# MCU_M_V1.net
KiCad netlist of a schematic drawn in Altium Designer
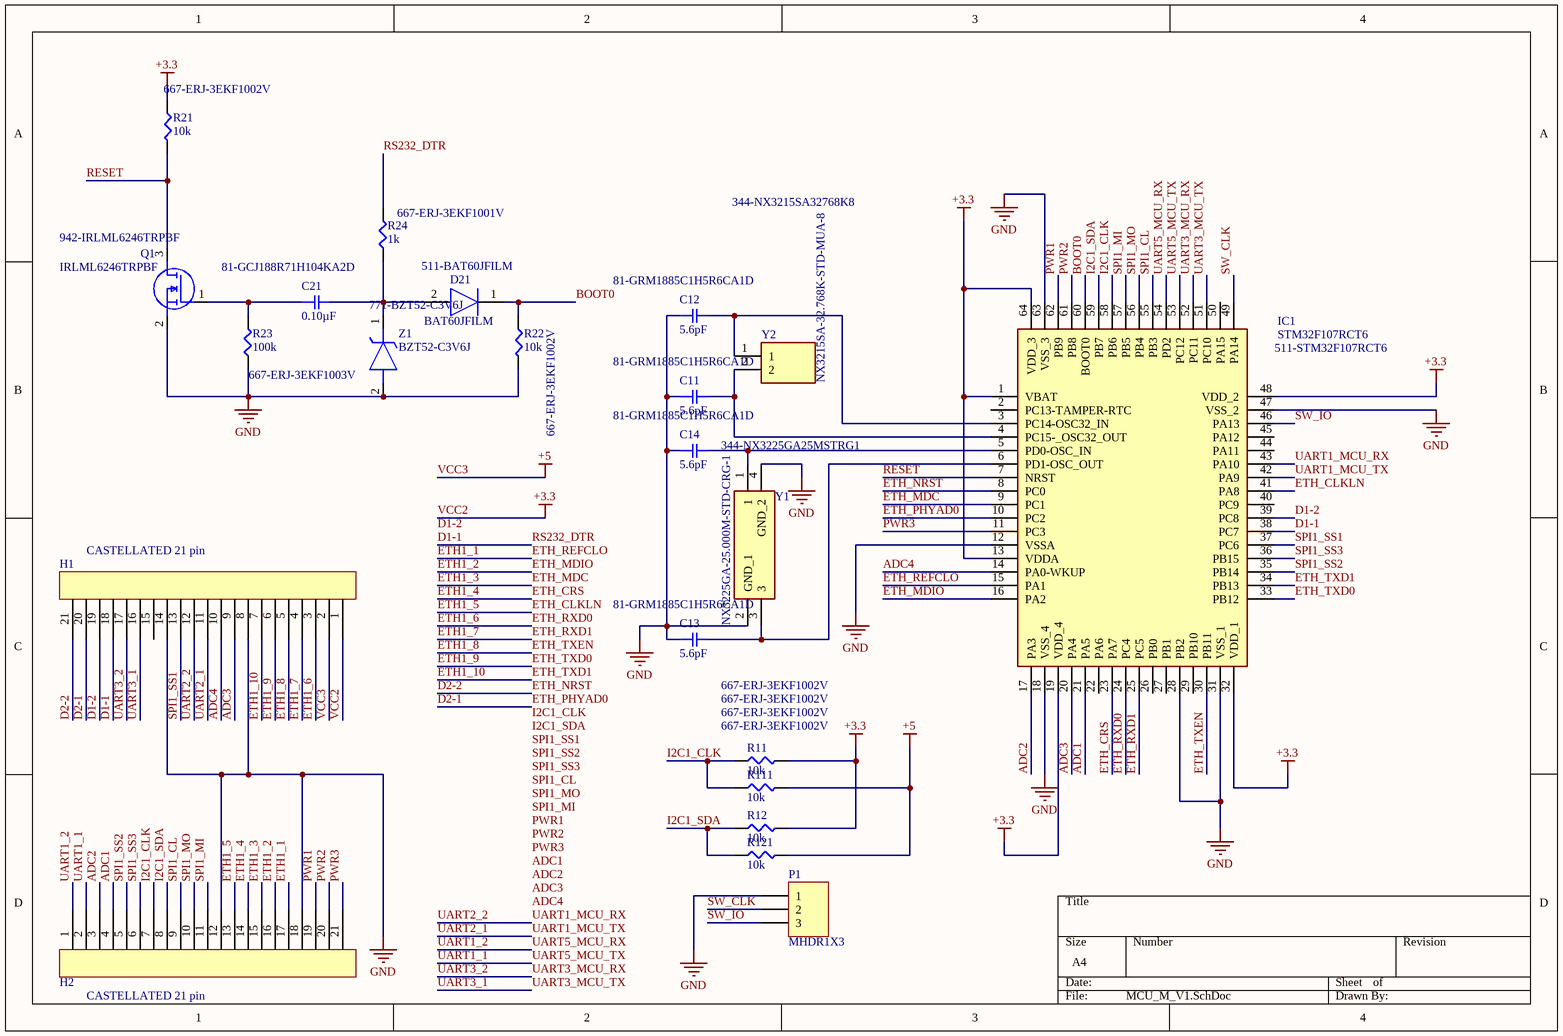
[diagram p0: MCU_M_V1.SchDoc]

(export (version "E")
  (design (tool "Eeschema 10.0.6"))
  (components
    (comp (ref "C11")
      (value "5.6pF")
      (footprint "SMD-0603C")
      (description "CAP CER 5.6PF 50V NP0 0603")
      (fields
        (field (name "DIGI-KEY PART NUMBER") "490-12723-1-ND")
        (field (name "PART NUMBER") "GRM1885C1H5R6CA01D")
        (field (name "SUPPLIER PART NUMBER 1") "81-GRM1885C1H5R6CA1D")
      )
      (libsource (lib "capacitor_murata_0603") (part "GRM1885C1H5R6CA01D"))
    )
    (comp (ref "C12")
      (value "5.6pF")
      (footprint "SMD-0603C")
      (description "CAP CER 5.6PF 50V NP0 0603")
      (fields
        (field (name "DIGI-KEY PART NUMBER") "490-12723-1-ND")
        (field (name "PART NUMBER") "GRM1885C1H5R6CA01D")
        (field (name "SUPPLIER PART NUMBER 1") "81-GRM1885C1H5R6CA1D")
      )
      (libsource (lib "capacitor_murata_0603") (part "GRM1885C1H5R6CA01D"))
    )
    (comp (ref "C13")
      (value "5.6pF")
      (footprint "SMD-0603C")
      (description "CAP CER 5.6PF 50V NP0 0603")
      (fields
        (field (name "DIGI-KEY PART NUMBER") "490-12723-1-ND")
        (field (name "PART NUMBER") "GRM1885C1H5R6CA01D")
        (field (name "SUPPLIER PART NUMBER 1") "81-GRM1885C1H5R6CA1D")
      )
      (libsource (lib "capacitor_murata_0603") (part "GRM1885C1H5R6CA01D"))
    )
    (comp (ref "C14")
      (value "5.6pF")
      (footprint "SMD-0603C")
      (description "CAP CER 5.6PF 50V NP0 0603")
      (fields
        (field (name "DIGI-KEY PART NUMBER") "490-12723-1-ND")
        (field (name "PART NUMBER") "GRM1885C1H5R6CA01D")
        (field (name "SUPPLIER PART NUMBER 1") "81-GRM1885C1H5R6CA1D")
      )
      (libsource (lib "capacitor_murata_0603") (part "GRM1885C1H5R6CA01D"))
    )
    (comp (ref "C21")
      (value "0.10µF")
      (footprint "SMD-0603C")
      (description "CAP CER 0.1UF 50V X7R 0603")
      (fields
        (field (name "DIGI-KEY PART NUMBER") "490-5798-1-ND")
        (field (name "PART NUMBER") "GCJ188R71H104KA12D")
        (field (name "SUPPLIER PART NUMBER 1") "81-GCJ188R71H104KA2D")
      )
      (libsource (lib "capacitor_murata_0603") (part "GCJ188R71H104KA12D"))
    )
    (comp (ref "D21")
      (value "BAT60JFILM")
      (footprint "SamacSys:SOD2513X117N")
      (description "Diode")
      (fields
        (field (name "MOUSER2 PART NUMBER") "511-BAT60JFILM")
        (field (name "SUPPLIER PART NUMBER 1") "511-BAT60JFILM")
      )
      (libsource (lib "*") (part "BAT60JFILM"))
    )
    (comp (ref "H1")
      (value "CASTELLATED 21 pin")
      (footprint "CASTELLATED 21 pin")
      (libsource (lib "USIB") (part "CASTELLATED 21 pin"))
    )
    (comp (ref "H2")
      (value "CASTELLATED 21 pin")
      (footprint "CASTELLATED 21 pin")
      (libsource (lib "") (part "CASTELLATED 21 pin_1"))
    )
    (comp (ref "IC1")
      (value "STM32F107RCT6")
      (footprint "SamacSys:QFP50P1200X1200X160-64N")
      (description "Integrated Circuit")
      (fields
        (field (name "MOUSER2 PART NUMBER") "511-STM32F107RCT6")
        (field (name "SUPPLIER PART NUMBER 1") "511-STM32F107RCT6")
      )
      (libsource (lib "*") (part "STM32F107RCT6"))
    )
    (comp (ref "P1")
      (value "MHDR1X3")
      (footprint "MHDR1X3")
      (description "Header, 3-Pin")
      (fields (field (name "PUBLISHER") "Altium Limited"))
      (libsource (lib "Miscellaneous Connectors") (part "MHDR1X3"))
    )
    (comp (ref "Q1")
      (value "IRLML6246TRPBF")
      (footprint "SamacSys:SOT95P237X112-3N")
      (description "MOSFET (N-Channel)")
      (fields (field (name "SUPPLIER PART NUMBER 1") "942-IRLML6246TRPBF"))
      (libsource (lib "*") (part "IRLML6246TRPBF"))
    )
    (comp (ref "R11")
      (value "10k")
      (footprint "SMD-0603-RES")
      (description "RES SMD 10K OHM 1% 1/10W 0603")
      (fields
        (field (name "PART NUMBER") "ERJ-3EKF1002V")
        (field (name "DIGI-KEY PART NUMBER") "P10.0KHCT-ND")
        (field (name "SUPPLIER PART NUMBER 1") "667-ERJ-3EKF1002V")
      )
      (libsource (lib "Panasonic_ERJ_0603") (part "ERJ-3EKF1002V"))
    )
    (comp (ref "R12")
      (value "10k")
      (footprint "SMD-0603-RES")
      (description "RES SMD 10K OHM 1% 1/10W 0603")
      (fields
        (field (name "PART NUMBER") "ERJ-3EKF1002V")
        (field (name "DIGI-KEY PART NUMBER") "P10.0KHCT-ND")
        (field (name "SUPPLIER PART NUMBER 1") "667-ERJ-3EKF1002V")
      )
      (libsource (lib "Panasonic_ERJ_0603") (part "ERJ-3EKF1002V"))
    )
    (comp (ref "R21")
      (value "10k")
      (footprint "SMD-0603-RES")
      (description "RES SMD 10K OHM 1% 1/10W 0603")
      (fields
        (field (name "PART NUMBER") "ERJ-3EKF1002V")
        (field (name "DIGI-KEY PART NUMBER") "P10.0KHCT-ND")
        (field (name "SUPPLIER PART NUMBER 1") "667-ERJ-3EKF1002V")
      )
      (libsource (lib "Panasonic_ERJ_0603") (part "ERJ-3EKF1002V"))
    )
    (comp (ref "R22")
      (value "10k")
      (footprint "SMD-0603-RES")
      (description "RES SMD 10K OHM 1% 1/10W 0603")
      (fields
        (field (name "PART NUMBER") "ERJ-3EKF1002V")
        (field (name "DIGI-KEY PART NUMBER") "P10.0KHCT-ND")
        (field (name "SUPPLIER PART NUMBER 1") "667-ERJ-3EKF1002V")
      )
      (libsource (lib "Panasonic_ERJ_0603") (part "ERJ-3EKF1002V"))
    )
    (comp (ref "R23")
      (value "100k")
      (footprint "SMD-0603-RES")
      (description "RES SMD 100K OHM 1% 1/10W 0603")
      (fields
        (field (name "PART NUMBER") "ERJ-3EKF1003V")
        (field (name "DIGI-KEY PART NUMBER") "P100KHCT-ND")
        (field (name "SUPPLIER PART NUMBER 1") "667-ERJ-3EKF1003V")
      )
      (libsource (lib "Panasonic_ERJ_0603") (part "ERJ-3EKF1003V"))
    )
    (comp (ref "R24")
      (value "1k")
      (footprint "SMD-0603-RES")
      (description "RES SMD 1K OHM 1% 1/10W 0603")
      (fields
        (field (name "PART NUMBER") "ERJ-3EKF1001V")
        (field (name "DIGI-KEY PART NUMBER") "P1.00KHCT-ND")
        (field (name "SUPPLIER PART NUMBER 1") "667-ERJ-3EKF1001V")
      )
      (libsource (lib "Panasonic_ERJ_0603") (part "ERJ-3EKF1001V"))
    )
    (comp (ref "R111")
      (value "10k")
      (footprint "SMD-0603-RES")
      (description "RES SMD 10K OHM 1% 1/10W 0603")
      (fields
        (field (name "PART NUMBER") "ERJ-3EKF1002V")
        (field (name "DIGI-KEY PART NUMBER") "P10.0KHCT-ND")
        (field (name "SUPPLIER PART NUMBER 1") "667-ERJ-3EKF1002V")
      )
      (libsource (lib "Panasonic_ERJ_0603") (part "ERJ-3EKF1002V"))
    )
    (comp (ref "R121")
      (value "10k")
      (footprint "SMD-0603-RES")
      (description "RES SMD 10K OHM 1% 1/10W 0603")
      (fields
        (field (name "PART NUMBER") "ERJ-3EKF1002V")
        (field (name "DIGI-KEY PART NUMBER") "P10.0KHCT-ND")
        (field (name "SUPPLIER PART NUMBER 1") "667-ERJ-3EKF1002V")
      )
      (libsource (lib "Panasonic_ERJ_0603") (part "ERJ-3EKF1002V"))
    )
    (comp (ref "Y1")
      (value "NX3225GA-25.000M-STD-CRG-1")
      (footprint "SamacSys:NX3225SA_1")
      (description "Crystal or Oscillator")
      (fields
        (field (name "MOUSER2 PART NUMBER") "344-NX3225GA25MSTRG1")
        (field (name "SUPPLIER PART NUMBER 1") "344-NX3225GA25MSTRG1")
      )
      (libsource (lib "*") (part "NX3225GA-25.000M-STD-CRG-1"))
    )
    (comp (ref "Y2")
      (value "NX3215SA-32.768K-STD-MUA-8")
      (footprint "SamacSys:NX3215SA")
      (description "Crystal or Oscillator")
      (fields
        (field (name "MOUSER2 PART NUMBER") "344-NX3215SA32768K8")
        (field (name "SUPPLIER PART NUMBER 1") "344-NX3215SA32768K8")
      )
      (libsource (lib "*") (part "NX3215SA-32.768K-STD-MUA-8"))
    )
    (comp (ref "Z1")
      (value "BZT52-C3V6J")
      (footprint "SamacSys:SOD123")
      (description "Zener Diode")
      (fields
        (field (name "MOUSER2 PART NUMBER") "771-BZT52-C3V6J")
        (field (name "SUPPLIER PART NUMBER 1") "771-BZT52-C3V6J")
      )
      (libsource (lib "*") (part "BZT52-C3V6J"))
    )
  )
  (nets
    (net (code "1") (name "+3.3") (class "Default")
      (node (ref "H1") (pin "1") (pintype "passive"))
      (node (ref "IC1") (pin "1") (pinfunction "VBAT_1") (pintype "passive"))
      (node (ref "IC1") (pin "13") (pinfunction "VDDA_13") (pintype "passive"))
      (node (ref "IC1") (pin "19") (pinfunction "VDD_4_19") (pintype "passive"))
      (node (ref "IC1") (pin "32") (pinfunction "VDD_1_32") (pintype "passive"))
      (node (ref "IC1") (pin "48") (pinfunction "VDD_2_48") (pintype "passive"))
      (node (ref "IC1") (pin "64") (pinfunction "VDD_3_64") (pintype "passive"))
      (node (ref "R11") (pin "2") (pinfunction "2_2") (pintype "passive"))
      (node (ref "R12") (pin "2") (pinfunction "2_2") (pintype "passive"))
      (node (ref "R21") (pin "1") (pinfunction "1_1") (pintype "passive"))
    )
    (net (code "2") (name "+5") (class "Default")
      (node (ref "H1") (pin "2") (pintype "passive"))
      (node (ref "R111") (pin "2") (pinfunction "2_2") (pintype "passive"))
      (node (ref "R121") (pin "2") (pinfunction "2_2") (pintype "passive"))
    )
    (net (code "3") (name "/ADC1") (class "Default")
      (node (ref "H2") (pin "4") (pintype "passive"))
      (node (ref "IC1") (pin "21") (pinfunction "PA5_21") (pintype "passive"))
    )
    (net (code "4") (name "/ADC2") (class "Default")
      (node (ref "H2") (pin "3") (pintype "passive"))
      (node (ref "IC1") (pin "17") (pinfunction "PA3_17") (pintype "passive"))
    )
    (net (code "5") (name "/ADC3") (class "Default")
      (node (ref "H1") (pin "9") (pintype "passive"))
      (node (ref "IC1") (pin "20") (pinfunction "PA4_20") (pintype "passive"))
    )
    (net (code "6") (name "/ADC4") (class "Default")
      (node (ref "H1") (pin "10") (pintype "passive"))
      (node (ref "IC1") (pin "14") (pinfunction "PA0-WKUP_14") (pintype "passive"))
    )
    (net (code "7") (name "/BOOT0") (class "Default")
      (node (ref "D21") (pin "1") (pinfunction "K_1") (pintype "passive"))
      (node (ref "IC1") (pin "60") (pinfunction "BOOT0_60") (pintype "passive"))
      (node (ref "R22") (pin "1") (pinfunction "1_1") (pintype "passive"))
    )
    (net (code "8") (name "/D1-1") (class "Default")
      (node (ref "H1") (pin "18") (pintype "passive"))
      (node (ref "IC1") (pin "38") (pinfunction "PC7_38") (pintype "passive"))
      (node (ref "R24") (pin "2") (pinfunction "2_2") (pintype "passive"))
    )
    (net (code "9") (name "/D1-2") (class "Default")
      (node (ref "H1") (pin "19") (pintype "passive"))
      (node (ref "IC1") (pin "39") (pinfunction "PC8_39") (pintype "passive"))
    )
    (net (code "10") (name "/D2-1") (class "Default")
      (node (ref "H1") (pin "20") (pintype "passive"))
      (node (ref "IC1") (pin "10") (pinfunction "PC2_10") (pintype "passive"))
    )
    (net (code "11") (name "/D2-2") (class "Default")
      (node (ref "H1") (pin "21") (pintype "passive"))
      (node (ref "IC1") (pin "8") (pinfunction "PC0_8") (pintype "passive"))
    )
    (net (code "12") (name "/ETH1_1") (class "Default")
      (node (ref "H2") (pin "17") (pintype "passive"))
      (node (ref "IC1") (pin "15") (pinfunction "PA1_15") (pintype "passive"))
    )
    (net (code "13") (name "/ETH1_2") (class "Default")
      (node (ref "H2") (pin "16") (pintype "passive"))
      (node (ref "IC1") (pin "16") (pinfunction "PA2_16") (pintype "passive"))
    )
    (net (code "14") (name "/ETH1_3") (class "Default")
      (node (ref "H2") (pin "15") (pintype "passive"))
      (node (ref "IC1") (pin "9") (pinfunction "PC1_9") (pintype "passive"))
    )
    (net (code "15") (name "/ETH1_4") (class "Default")
      (node (ref "H2") (pin "14") (pintype "passive"))
      (node (ref "IC1") (pin "23") (pinfunction "PA7_23") (pintype "passive"))
    )
    (net (code "16") (name "/ETH1_5") (class "Default")
      (node (ref "H2") (pin "13") (pintype "passive"))
      (node (ref "IC1") (pin "41") (pinfunction "PA8_41") (pintype "passive"))
    )
    (net (code "17") (name "/ETH1_6") (class "Default")
      (node (ref "H1") (pin "3") (pintype "passive"))
      (node (ref "IC1") (pin "24") (pinfunction "PC4_24") (pintype "passive"))
    )
    (net (code "18") (name "/ETH1_7") (class "Default")
      (node (ref "H1") (pin "4") (pintype "passive"))
      (node (ref "IC1") (pin "25") (pinfunction "PC5_25") (pintype "passive"))
    )
    (net (code "19") (name "/ETH1_8") (class "Default")
      (node (ref "H1") (pin "5") (pintype "passive"))
      (node (ref "IC1") (pin "30") (pinfunction "PB11_30") (pintype "passive"))
    )
    (net (code "20") (name "/ETH1_9") (class "Default")
      (node (ref "H1") (pin "6") (pintype "passive"))
      (node (ref "IC1") (pin "33") (pinfunction "PB12_33") (pintype "passive"))
    )
    (net (code "21") (name "/ETH1_10") (class "Default")
      (node (ref "H1") (pin "7") (pintype "passive"))
      (node (ref "IC1") (pin "34") (pinfunction "PB13_34") (pintype "passive"))
    )
    (net (code "22") (name "/I2C1_CLK") (class "Default")
      (node (ref "H2") (pin "7") (pintype "passive"))
      (node (ref "IC1") (pin "58") (pinfunction "PB6_58") (pintype "passive"))
      (node (ref "R11") (pin "1") (pinfunction "1_1") (pintype "passive"))
      (node (ref "R111") (pin "1") (pinfunction "1_1") (pintype "passive"))
    )
    (net (code "23") (name "/I2C1_SDA") (class "Default")
      (node (ref "H2") (pin "8") (pintype "passive"))
      (node (ref "IC1") (pin "59") (pinfunction "PB7_59") (pintype "passive"))
      (node (ref "R12") (pin "1") (pinfunction "1_1") (pintype "passive"))
      (node (ref "R121") (pin "1") (pinfunction "1_1") (pintype "passive"))
    )
    (net (code "24") (name "/PWR1") (class "Default")
      (node (ref "H2") (pin "19") (pintype "passive"))
      (node (ref "IC1") (pin "62") (pinfunction "PB9_62") (pintype "passive"))
    )
    (net (code "25") (name "/PWR2") (class "Default")
      (node (ref "H2") (pin "20") (pintype "passive"))
      (node (ref "IC1") (pin "61") (pinfunction "PB8_61") (pintype "passive"))
    )
    (net (code "26") (name "/PWR3") (class "Default")
      (node (ref "H2") (pin "21") (pintype "passive"))
      (node (ref "IC1") (pin "11") (pinfunction "PC3_11") (pintype "passive"))
    )
    (net (code "27") (name "/RESET") (class "Default")
      (node (ref "IC1") (pin "7") (pinfunction "NRST_7") (pintype "passive"))
      (node (ref "Q1") (pin "3") (pinfunction "D_3") (pintype "passive"))
      (node (ref "R21") (pin "2") (pinfunction "2_2") (pintype "passive"))
    )
    (net (code "28") (name "/SPI1_CL") (class "Default")
      (node (ref "H2") (pin "9") (pintype "passive"))
      (node (ref "IC1") (pin "55") (pinfunction "PB3_55") (pintype "passive"))
    )
    (net (code "29") (name "/SPI1_MI") (class "Default")
      (node (ref "H2") (pin "11") (pintype "passive"))
      (node (ref "IC1") (pin "57") (pinfunction "PB5_57") (pintype "passive"))
    )
    (net (code "30") (name "/SPI1_MO") (class "Default")
      (node (ref "H2") (pin "10") (pintype "passive"))
      (node (ref "IC1") (pin "56") (pinfunction "PB4_56") (pintype "passive"))
    )
    (net (code "31") (name "/SPI1_SS1") (class "Default")
      (node (ref "H1") (pin "13") (pintype "passive"))
      (node (ref "IC1") (pin "37") (pinfunction "PC6_37") (pintype "passive"))
    )
    (net (code "32") (name "/SPI1_SS2") (class "Default")
      (node (ref "H2") (pin "5") (pintype "passive"))
      (node (ref "IC1") (pin "35") (pinfunction "PB14_35") (pintype "passive"))
    )
    (net (code "33") (name "/SPI1_SS3") (class "Default")
      (node (ref "H2") (pin "6") (pintype "passive"))
      (node (ref "IC1") (pin "36") (pinfunction "PB15_36") (pintype "passive"))
    )
    (net (code "34") (name "/SW_CLK") (class "Default")
      (node (ref "IC1") (pin "49") (pinfunction "PA14_49") (pintype "passive"))
      (node (ref "P1") (pin "2") (pinfunction "2_2") (pintype "passive"))
    )
    (net (code "35") (name "/SW_IO") (class "Default")
      (node (ref "IC1") (pin "46") (pinfunction "PA13_46") (pintype "passive"))
      (node (ref "P1") (pin "3") (pinfunction "3_3") (pintype "passive"))
    )
    (net (code "36") (name "/UART1_1") (class "Default")
      (node (ref "H2") (pin "2") (pintype "passive"))
      (node (ref "IC1") (pin "53") (pinfunction "PC12_53") (pintype "passive"))
    )
    (net (code "37") (name "/UART1_2") (class "Default")
      (node (ref "H2") (pin "1") (pintype "passive"))
      (node (ref "IC1") (pin "54") (pinfunction "PD2_54") (pintype "passive"))
    )
    (net (code "38") (name "/UART1_MCU_RX") (class "Default")
      (node (ref "H1") (pin "12") (pintype "passive"))
      (node (ref "IC1") (pin "43") (pinfunction "PA10_43") (pintype "passive"))
    )
    (net (code "39") (name "/UART1_MCU_TX") (class "Default")
      (node (ref "H1") (pin "11") (pintype "passive"))
      (node (ref "IC1") (pin "42") (pinfunction "PA9_42") (pintype "passive"))
    )
    (net (code "40") (name "/UART3_1") (class "Default")
      (node (ref "H1") (pin "16") (pintype "passive"))
      (node (ref "IC1") (pin "51") (pinfunction "PC10_51") (pintype "passive"))
    )
    (net (code "41") (name "/UART3_2") (class "Default")
      (node (ref "H1") (pin "17") (pintype "passive"))
      (node (ref "IC1") (pin "52") (pinfunction "PC11_52") (pintype "passive"))
    )
    (net (code "42") (name "GND") (class "Default")
      (node (ref "C11") (pin "1") (pinfunction "1_1") (pintype "passive"))
      (node (ref "C12") (pin "1") (pinfunction "1_1") (pintype "passive"))
      (node (ref "C13") (pin "1") (pinfunction "1_1") (pintype "passive"))
      (node (ref "C14") (pin "1") (pinfunction "1_1") (pintype "passive"))
      (node (ref "H1") (pin "14") (pintype "passive"))
      (node (ref "H1") (pin "8") (pintype "passive"))
      (node (ref "H2") (pin "12") (pintype "passive"))
      (node (ref "H2") (pin "18") (pintype "passive"))
      (node (ref "IC1") (pin "12") (pinfunction "VSSA_12") (pintype "passive"))
      (node (ref "IC1") (pin "18") (pinfunction "VSS_4_18") (pintype "passive"))
      (node (ref "IC1") (pin "28") (pinfunction "PB2_28") (pintype "passive"))
      (node (ref "IC1") (pin "31") (pinfunction "VSS_1_31") (pintype "passive"))
      (node (ref "IC1") (pin "47") (pinfunction "VSS_2_47") (pintype "passive"))
      (node (ref "IC1") (pin "63") (pinfunction "VSS_3_63") (pintype "passive"))
      (node (ref "P1") (pin "1") (pinfunction "1_1") (pintype "passive"))
      (node (ref "Q1") (pin "2") (pinfunction "S_2") (pintype "passive"))
      (node (ref "R22") (pin "2") (pinfunction "2_2") (pintype "passive"))
      (node (ref "R23") (pin "1") (pinfunction "1_1") (pintype "passive"))
      (node (ref "Y1") (pin "2") (pinfunction "GND_1_2") (pintype "passive"))
      (node (ref "Y1") (pin "4") (pinfunction "GND_2_4") (pintype "passive"))
      (node (ref "Z1") (pin "2") (pinfunction "A_2") (pintype "passive"))
    )
    (net (code "43") (name "Net-(D21-A)") (class "Default")
      (node (ref "C21") (pin "2") (pinfunction "2_2") (pintype "passive"))
      (node (ref "D21") (pin "2") (pinfunction "A_2") (pintype "passive"))
      (node (ref "R24") (pin "1") (pinfunction "1_1") (pintype "passive"))
      (node (ref "Z1") (pin "1") (pinfunction "K_1") (pintype "passive"))
    )
    (net (code "44") (name "Net-(IC1-PC14-OSC32_IN)") (class "Default")
      (node (ref "C12") (pin "2") (pinfunction "2_2") (pintype "passive"))
      (node (ref "IC1") (pin "3") (pinfunction "PC14-OSC32_IN_3") (pintype "passive"))
      (node (ref "Y2") (pin "1") (pinfunction "1_1") (pintype "passive"))
    )
    (net (code "45") (name "Net-(IC1-PC15-_OSC32_OUT)") (class "Default")
      (node (ref "C11") (pin "2") (pinfunction "2_2") (pintype "passive"))
      (node (ref "IC1") (pin "4") (pinfunction "PC15-_OSC32_OUT_4") (pintype "passive"))
      (node (ref "Y2") (pin "2") (pinfunction "2_2") (pintype "passive"))
    )
    (net (code "46") (name "Net-(IC1-PD0-OSC_IN)") (class "Default")
      (node (ref "C14") (pin "2") (pinfunction "2_2") (pintype "passive"))
      (node (ref "IC1") (pin "5") (pinfunction "PD0-OSC_IN_5") (pintype "passive"))
      (node (ref "Y1") (pin "1") (pinfunction "1_1") (pintype "passive"))
    )
    (net (code "47") (name "Net-(IC1-PD1-OSC_OUT)") (class "Default")
      (node (ref "C13") (pin "2") (pinfunction "2_2") (pintype "passive"))
      (node (ref "IC1") (pin "6") (pinfunction "PD1-OSC_OUT_6") (pintype "passive"))
      (node (ref "Y1") (pin "3") (pinfunction "3_3") (pintype "passive"))
    )
    (net (code "48") (name "Net-(Q1-G)") (class "Default")
      (node (ref "C21") (pin "1") (pinfunction "1_1") (pintype "passive"))
      (node (ref "Q1") (pin "1") (pinfunction "G_1") (pintype "passive"))
      (node (ref "R23") (pin "2") (pinfunction "2_2") (pintype "passive"))
    )
    (net (code "49") (name "unconnected-(H1-Pad15)") (class "Default")
      (node (ref "H1") (pin "15") (pintype "passive"))
    )
    (net (code "50") (name "unconnected-(IC1-PA6-Pad22)") (class "Default")
      (node (ref "IC1") (pin "22") (pinfunction "PA6_22") (pintype "passive"))
    )
    (net (code "51") (name "unconnected-(IC1-PA11-Pad44)") (class "Default")
      (node (ref "IC1") (pin "44") (pinfunction "PA11_44") (pintype "passive"))
    )
    (net (code "52") (name "unconnected-(IC1-PA12-Pad45)") (class "Default")
      (node (ref "IC1") (pin "45") (pinfunction "PA12_45") (pintype "passive"))
    )
    (net (code "53") (name "unconnected-(IC1-PA15-Pad50)") (class "Default")
      (node (ref "IC1") (pin "50") (pinfunction "PA15_50") (pintype "passive"))
    )
    (net (code "54") (name "unconnected-(IC1-PB0-Pad26)") (class "Default")
      (node (ref "IC1") (pin "26") (pinfunction "PB0_26") (pintype "passive"))
    )
    (net (code "55") (name "unconnected-(IC1-PB1-Pad27)") (class "Default")
      (node (ref "IC1") (pin "27") (pinfunction "PB1_27") (pintype "passive"))
    )
    (net (code "56") (name "unconnected-(IC1-PB10-Pad29)") (class "Default")
      (node (ref "IC1") (pin "29") (pinfunction "PB10_29") (pintype "passive"))
    )
    (net (code "57") (name "unconnected-(IC1-PC9-Pad40)") (class "Default")
      (node (ref "IC1") (pin "40") (pinfunction "PC9_40") (pintype "passive"))
    )
    (net (code "58") (name "unconnected-(IC1-PC13-TAMPER-RTC-Pad2)") (class "Default")
      (node (ref "IC1") (pin "2") (pinfunction "PC13-TAMPER-RTC_2") (pintype "passive"))
    )
  )
)
